# Placa_principal.net
KiCad netlist of a schematic drawn in EAGLE
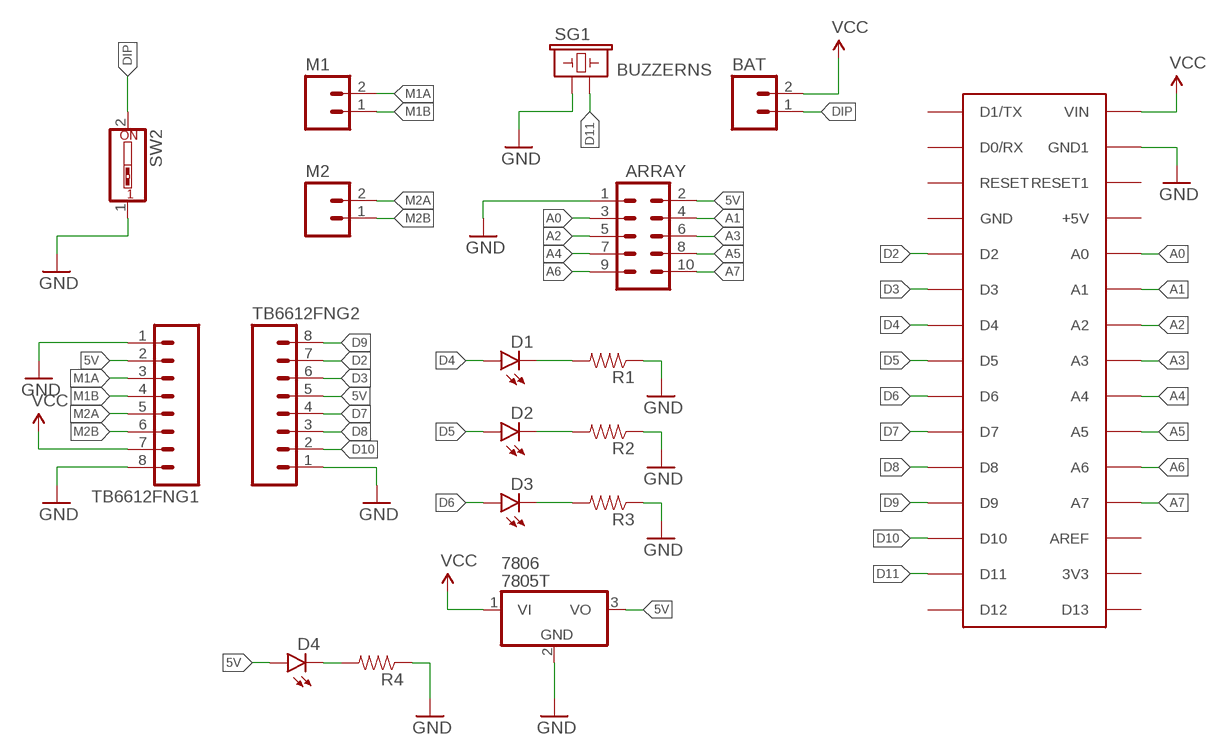
[diagram p0: schematic, sheet 1]

(export (version "E")
  (design (tool "Eeschema 10.0.6"))
  (components
    (comp (ref "7806")
      (value "7805T")
      (footprint "eagle-import:TO220H")
      (libsource (lib "eagle-import") (part "78T05"))
    )
    (comp (ref "ARRAY")
      (value "M05X2PTH")
      (footprint "eagle-import:AVR_ICSP")
      (libsource (lib "eagle-import") (part "M05X2PTH"))
    )
    (comp (ref "BAT")
      (value "M02PTH")
      (footprint "eagle-import:1X02")
      (libsource (lib "eagle-import") (part "M02PTH"))
    )
    (comp (ref "D1")
      (value "LED5MM")
      (footprint "eagle-import:LED5MM")
      (libsource (lib "eagle-import") (part "LED5MM"))
    )
    (comp (ref "D2")
      (value "LED5MM")
      (footprint "eagle-import:LED5MM")
      (libsource (lib "eagle-import") (part "LED5MM"))
    )
    (comp (ref "D3")
      (value "LED5MM")
      (footprint "eagle-import:LED5MM")
      (libsource (lib "eagle-import") (part "LED5MM"))
    )
    (comp (ref "D4")
      (value "LED5MM")
      (footprint "eagle-import:LED5MM")
      (libsource (lib "eagle-import") (part "LED5MM"))
    )
    (comp (ref "M1")
      (value "M02JST-PTH-VERT")
      (footprint "eagle-import:JST-2-PTH-VERT")
      (libsource (lib "eagle-import") (part "M02JST-PTH-VERT"))
    )
    (comp (ref "M2")
      (value "M02JST-PTH-VERT")
      (footprint "eagle-import:JST-2-PTH-VERT")
      (libsource (lib "eagle-import") (part "M02JST-PTH-VERT"))
    )
    (comp (ref "R1")
      (value "RESISTOREZ")
      (footprint "eagle-import:AXIAL-0.3EZ")
      (libsource (lib "eagle-import") (part "RESISTOREZ"))
    )
    (comp (ref "R2")
      (value "RESISTOREZ")
      (footprint "eagle-import:AXIAL-0.3EZ")
      (libsource (lib "eagle-import") (part "RESISTOREZ"))
    )
    (comp (ref "R3")
      (value "RESISTOREZ")
      (footprint "eagle-import:AXIAL-0.3EZ")
      (libsource (lib "eagle-import") (part "RESISTOREZ"))
    )
    (comp (ref "R4")
      (value "RESISTOREZ")
      (footprint "eagle-import:AXIAL-0.3EZ")
      (libsource (lib "eagle-import") (part "RESISTOREZ"))
    )
    (comp (ref "SG1")
      (value "BUZZERNS")
      (footprint "eagle-import:BUZZER-12MM-NS")
      (libsource (lib "eagle-import") (part "BUZZERNS"))
    )
    (comp (ref "SW2")
      (value "SW_DIP-1")
      (footprint "eagle-import:EDG-01")
      (libsource (lib "eagle-import") (part "SW_DIP-1"))
    )
    (comp (ref "TB6612FNG1")
      (value "M08")
      (footprint "eagle-import:1X08_ROUND")
      (libsource (lib "eagle-import") (part "M08"))
    )
    (comp (ref "TB6612FNG2")
      (value "M08")
      (footprint "eagle-import:1X08_ROUND")
      (libsource (lib "eagle-import") (part "M08"))
    )
    (comp (ref "U$2")
      (value "ARDUINONANO")
      (footprint "eagle-import:PDIP-32")
      (libsource (lib "eagle-import") (part "ARDUINONANO"))
    )
  )
  (nets
    (net (code "1") (name "5V") (class "Default")
      (node (ref "7806") (pin "3") (pinfunction "VO_3") (pintype "passive"))
      (node (ref "ARRAY") (pin "2") (pinfunction "2_2") (pintype "passive"))
      (node (ref "D4") (pin "A") (pinfunction "A_A") (pintype "passive"))
      (node (ref "TB6612FNG1") (pin "2") (pinfunction "2_2") (pintype "passive"))
      (node (ref "TB6612FNG2") (pin "5") (pinfunction "5_5") (pintype "passive"))
    )
    (net (code "2") (name "A0") (class "Default")
      (node (ref "ARRAY") (pin "3") (pinfunction "3_3") (pintype "passive"))
      (node (ref "U$2") (pin "A0") (pinfunction "A0_A0") (pintype "bidirectional"))
    )
    (net (code "3") (name "A1") (class "Default")
      (node (ref "ARRAY") (pin "4") (pinfunction "4_4") (pintype "passive"))
      (node (ref "U$2") (pin "A1") (pinfunction "A1_A1") (pintype "bidirectional"))
    )
    (net (code "4") (name "A2") (class "Default")
      (node (ref "ARRAY") (pin "5") (pinfunction "5_5") (pintype "passive"))
      (node (ref "U$2") (pin "A2") (pinfunction "A2_A2") (pintype "bidirectional"))
    )
    (net (code "5") (name "A3") (class "Default")
      (node (ref "ARRAY") (pin "6") (pinfunction "6_6") (pintype "passive"))
      (node (ref "U$2") (pin "A3") (pinfunction "A3_A3") (pintype "bidirectional"))
    )
    (net (code "6") (name "A4") (class "Default")
      (node (ref "ARRAY") (pin "7") (pinfunction "7_7") (pintype "passive"))
      (node (ref "U$2") (pin "A4") (pinfunction "A4_A4") (pintype "bidirectional"))
    )
    (net (code "7") (name "A5") (class "Default")
      (node (ref "ARRAY") (pin "8") (pinfunction "8_8") (pintype "passive"))
      (node (ref "U$2") (pin "A5") (pinfunction "A5_A5") (pintype "bidirectional"))
    )
    (net (code "8") (name "A6") (class "Default")
      (node (ref "ARRAY") (pin "9") (pinfunction "9_9") (pintype "passive"))
      (node (ref "U$2") (pin "A6") (pinfunction "A6_A6") (pintype "bidirectional"))
    )
    (net (code "9") (name "A7") (class "Default")
      (node (ref "ARRAY") (pin "10") (pinfunction "10_10") (pintype "passive"))
      (node (ref "U$2") (pin "A7") (pinfunction "A7_A7") (pintype "bidirectional"))
    )
    (net (code "10") (name "D2") (class "Default")
      (node (ref "TB6612FNG2") (pin "7") (pinfunction "7_7") (pintype "passive"))
      (node (ref "U$2") (pin "D2") (pinfunction "D2_D2") (pintype "bidirectional"))
    )
    (net (code "11") (name "D3") (class "Default")
      (node (ref "TB6612FNG2") (pin "6") (pinfunction "6_6") (pintype "passive"))
      (node (ref "U$2") (pin "D3") (pinfunction "D3_D3") (pintype "bidirectional"))
    )
    (net (code "12") (name "D4") (class "Default")
      (node (ref "D1") (pin "A") (pinfunction "A_A") (pintype "passive"))
      (node (ref "U$2") (pin "D4") (pinfunction "D4_D4") (pintype "bidirectional"))
    )
    (net (code "13") (name "D5") (class "Default")
      (node (ref "D2") (pin "A") (pinfunction "A_A") (pintype "passive"))
      (node (ref "U$2") (pin "D5") (pinfunction "D5_D5") (pintype "bidirectional"))
    )
    (net (code "14") (name "D6") (class "Default")
      (node (ref "D3") (pin "A") (pinfunction "A_A") (pintype "passive"))
      (node (ref "U$2") (pin "D6") (pinfunction "D6_D6") (pintype "bidirectional"))
    )
    (net (code "15") (name "D7") (class "Default")
      (node (ref "TB6612FNG2") (pin "4") (pinfunction "4_4") (pintype "passive"))
      (node (ref "U$2") (pin "D7") (pinfunction "D7_D7") (pintype "bidirectional"))
    )
    (net (code "16") (name "D8") (class "Default")
      (node (ref "TB6612FNG2") (pin "3") (pinfunction "3_3") (pintype "passive"))
      (node (ref "U$2") (pin "D8") (pinfunction "D8_D8") (pintype "bidirectional"))
    )
    (net (code "17") (name "D9") (class "Default")
      (node (ref "TB6612FNG2") (pin "8") (pinfunction "8_8") (pintype "passive"))
      (node (ref "U$2") (pin "D9") (pinfunction "D9_D9") (pintype "bidirectional"))
    )
    (net (code "18") (name "D10") (class "Default")
      (node (ref "TB6612FNG2") (pin "2") (pinfunction "2_2") (pintype "passive"))
      (node (ref "U$2") (pin "D10") (pinfunction "D10_D10") (pintype "bidirectional"))
    )
    (net (code "19") (name "D11") (class "Default")
      (node (ref "SG1") (pin "-") (pinfunction "2_-") (pintype "passive"))
      (node (ref "U$2") (pin "D11") (pinfunction "D11_D11") (pintype "bidirectional"))
    )
    (net (code "20") (name "DIP") (class "Default")
      (node (ref "BAT") (pin "1") (pinfunction "1_1") (pintype "passive"))
      (node (ref "SW2") (pin "2") (pinfunction "2_2") (pintype "passive"))
    )
    (net (code "21") (name "GND") (class "Default")
      (node (ref "7806") (pin "2") (pinfunction "GND_2") (pintype "passive"))
      (node (ref "ARRAY") (pin "1") (pinfunction "1_1") (pintype "passive"))
      (node (ref "R1") (pin "P$1") (pinfunction "1_P$1") (pintype "passive"))
      (node (ref "R2") (pin "P$1") (pinfunction "1_P$1") (pintype "passive"))
      (node (ref "R3") (pin "P$1") (pinfunction "1_P$1") (pintype "passive"))
      (node (ref "R4") (pin "P$1") (pinfunction "1_P$1") (pintype "passive"))
      (node (ref "SG1") (pin "+") (pinfunction "1_+") (pintype "passive"))
      (node (ref "SW2") (pin "1") (pinfunction "1_1") (pintype "passive"))
      (node (ref "TB6612FNG1") (pin "1") (pinfunction "1_1") (pintype "passive"))
      (node (ref "TB6612FNG1") (pin "8") (pinfunction "8_8") (pintype "passive"))
      (node (ref "TB6612FNG2") (pin "1") (pinfunction "1_1") (pintype "passive"))
      (node (ref "U$2") (pin "GND1") (pinfunction "GND1_GND1") (pintype "bidirectional"))
    )
    (net (code "22") (name "M1A") (class "Default")
      (node (ref "M1") (pin "2") (pinfunction "2_2") (pintype "passive"))
      (node (ref "TB6612FNG1") (pin "3") (pinfunction "3_3") (pintype "passive"))
    )
    (net (code "23") (name "M1B") (class "Default")
      (node (ref "M1") (pin "1") (pinfunction "1_1") (pintype "passive"))
      (node (ref "TB6612FNG1") (pin "4") (pinfunction "4_4") (pintype "passive"))
    )
    (net (code "24") (name "M2A") (class "Default")
      (node (ref "M2") (pin "2") (pinfunction "2_2") (pintype "passive"))
      (node (ref "TB6612FNG1") (pin "5") (pinfunction "5_5") (pintype "passive"))
    )
    (net (code "25") (name "M2B") (class "Default")
      (node (ref "M2") (pin "1") (pinfunction "1_1") (pintype "passive"))
      (node (ref "TB6612FNG1") (pin "6") (pinfunction "6_6") (pintype "passive"))
    )
    (net (code "26") (name "Net-(D1-C)") (class "Default")
      (node (ref "D1") (pin "K") (pinfunction "C_K") (pintype "passive"))
      (node (ref "R1") (pin "P$2") (pinfunction "2_P$2") (pintype "passive"))
    )
    (net (code "27") (name "Net-(D2-C)") (class "Default")
      (node (ref "D2") (pin "K") (pinfunction "C_K") (pintype "passive"))
      (node (ref "R2") (pin "P$2") (pinfunction "2_P$2") (pintype "passive"))
    )
    (net (code "28") (name "Net-(D3-C)") (class "Default")
      (node (ref "D3") (pin "K") (pinfunction "C_K") (pintype "passive"))
      (node (ref "R3") (pin "P$2") (pinfunction "2_P$2") (pintype "passive"))
    )
    (net (code "29") (name "Net-(D4-C)") (class "Default")
      (node (ref "D4") (pin "K") (pinfunction "C_K") (pintype "passive"))
      (node (ref "R4") (pin "P$2") (pinfunction "2_P$2") (pintype "passive"))
    )
    (net (code "30") (name "VCC") (class "Default")
      (node (ref "7806") (pin "1") (pinfunction "VI_1") (pintype "input"))
      (node (ref "BAT") (pin "2") (pinfunction "2_2") (pintype "passive"))
      (node (ref "TB6612FNG1") (pin "7") (pinfunction "7_7") (pintype "passive"))
      (node (ref "U$2") (pin "VIN") (pinfunction "VIN_VIN") (pintype "bidirectional"))
    )
    (net (code "31") (name "unconnected-(U$2-Pad+5V)") (class "Default")
      (node (ref "U$2") (pin "+5V") (pinfunction "+5V_+5V") (pintype "bidirectional"))
    )
    (net (code "32") (name "unconnected-(U$2-Pad3V3)") (class "Default")
      (node (ref "U$2") (pin "3V3") (pinfunction "3V3_3V3") (pintype "bidirectional"))
    )
    (net (code "33") (name "unconnected-(U$2-PadAREF)") (class "Default")
      (node (ref "U$2") (pin "AREF") (pinfunction "AREF_AREF") (pintype "bidirectional"))
    )
    (net (code "34") (name "unconnected-(U$2-PadD0{slash}RX)") (class "Default")
      (node (ref "U$2") (pin "D0/RX") (pinfunction "D0/RX_D0/RX") (pintype "bidirectional"))
    )
    (net (code "35") (name "unconnected-(U$2-PadD1{slash}TX)") (class "Default")
      (node (ref "U$2") (pin "D1/TX") (pinfunction "D1/TX_D1/TX") (pintype "bidirectional"))
    )
    (net (code "36") (name "unconnected-(U$2-PadD12)") (class "Default")
      (node (ref "U$2") (pin "D12") (pinfunction "D12_D12") (pintype "bidirectional"))
    )
    (net (code "37") (name "unconnected-(U$2-PadD13)") (class "Default")
      (node (ref "U$2") (pin "D13") (pinfunction "D13_D13") (pintype "bidirectional"))
    )
    (net (code "38") (name "unconnected-(U$2-PadGND)") (class "Default")
      (node (ref "U$2") (pin "GND") (pinfunction "GND_GND") (pintype "bidirectional"))
    )
    (net (code "39") (name "unconnected-(U$2-PadRESET)") (class "Default")
      (node (ref "U$2") (pin "RESET") (pinfunction "RESET_RESET") (pintype "bidirectional"))
    )
    (net (code "40") (name "unconnected-(U$2-PadRESET1)") (class "Default")
      (node (ref "U$2") (pin "RESET1") (pinfunction "RESET1_RESET1") (pintype "bidirectional"))
    )
  )
)
